# controller_rev4_3.net
KiCad netlist of a schematic drawn in EAGLE
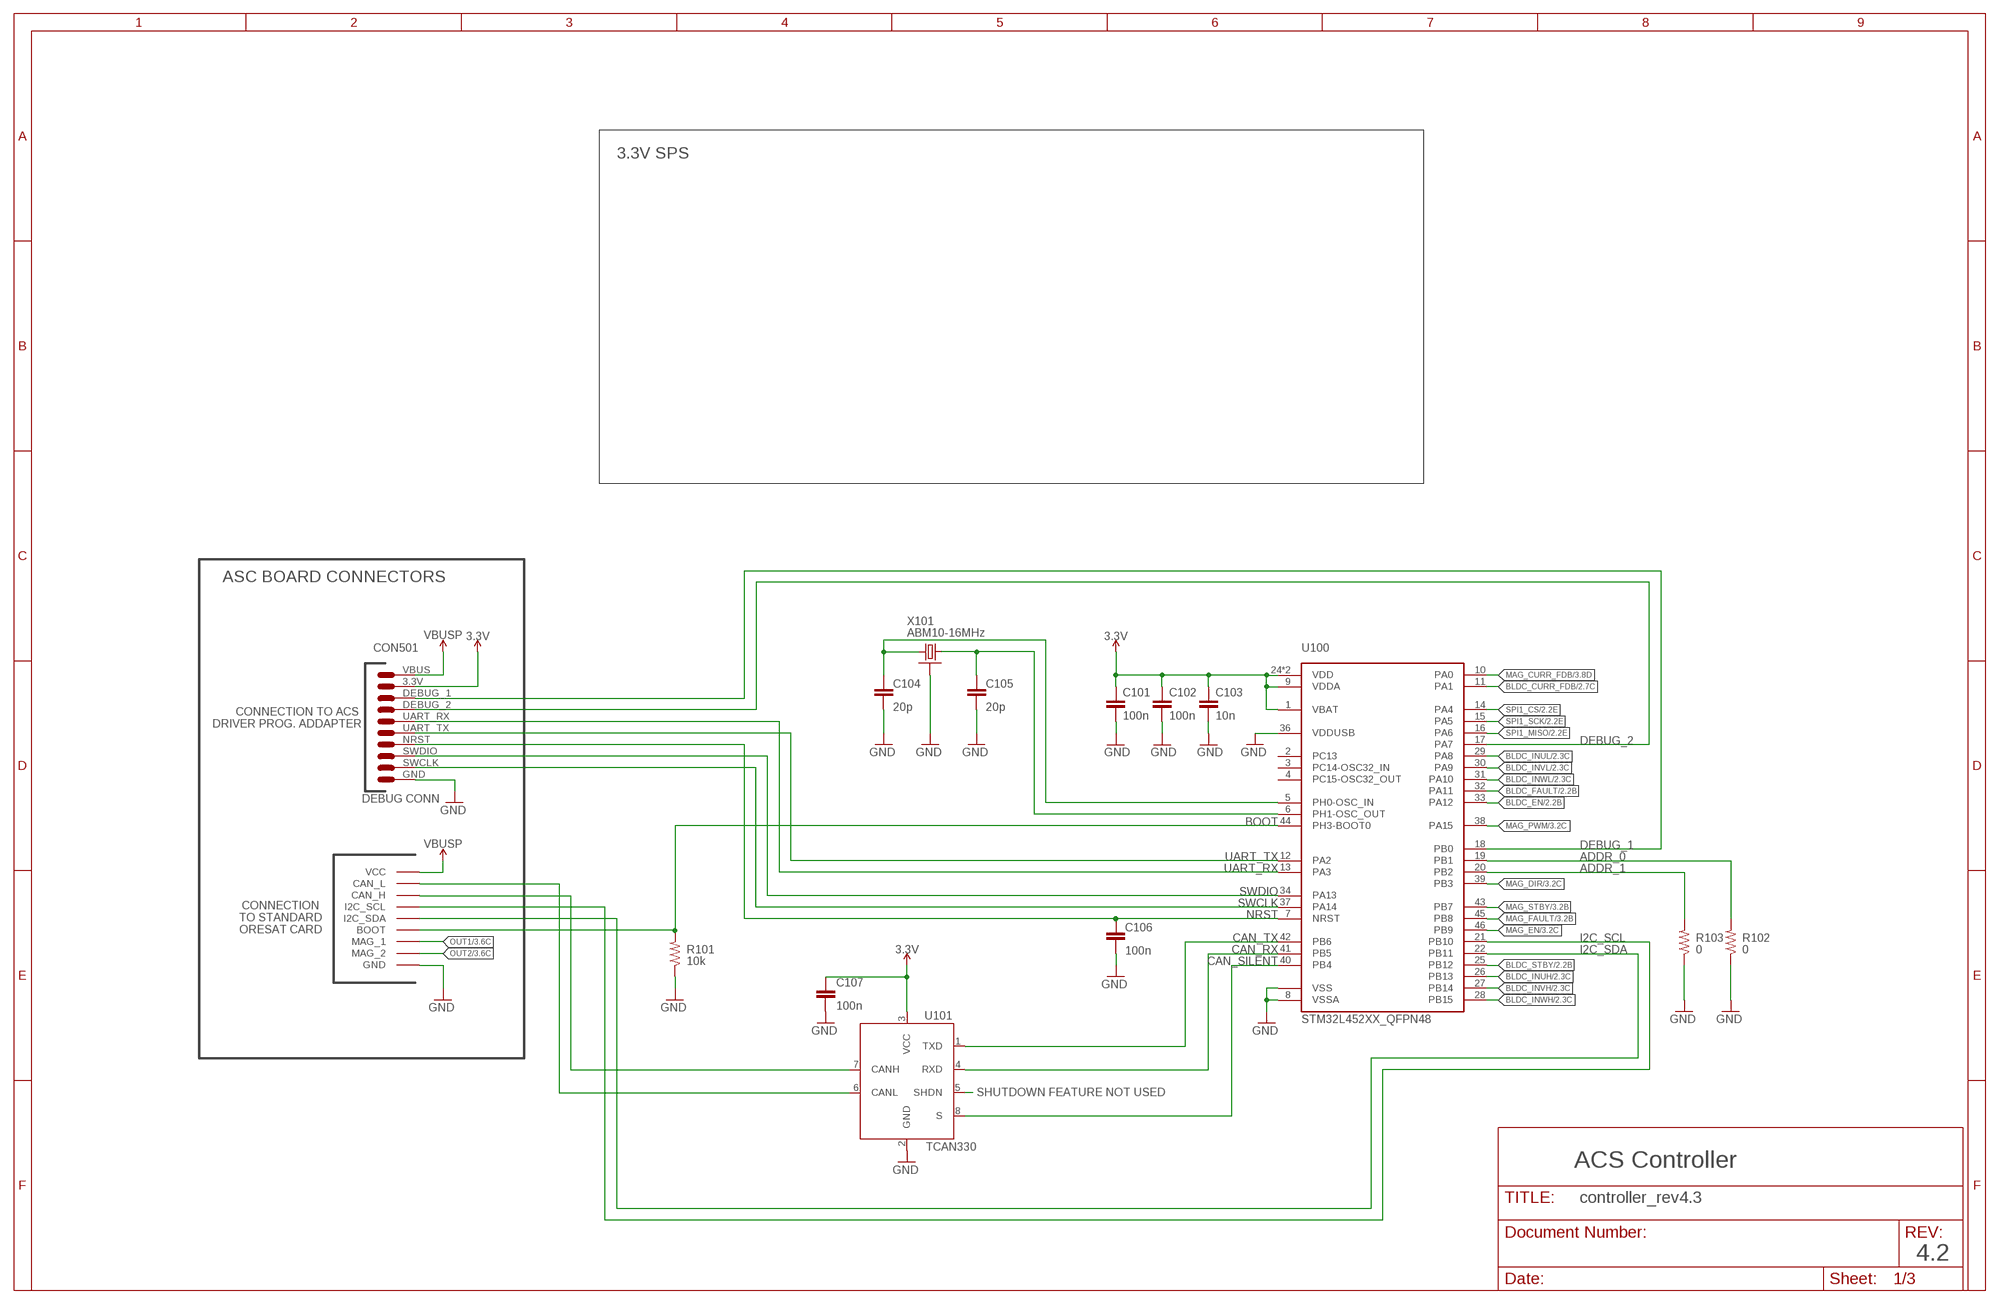
[diagram p0: schematic, sheet 1]
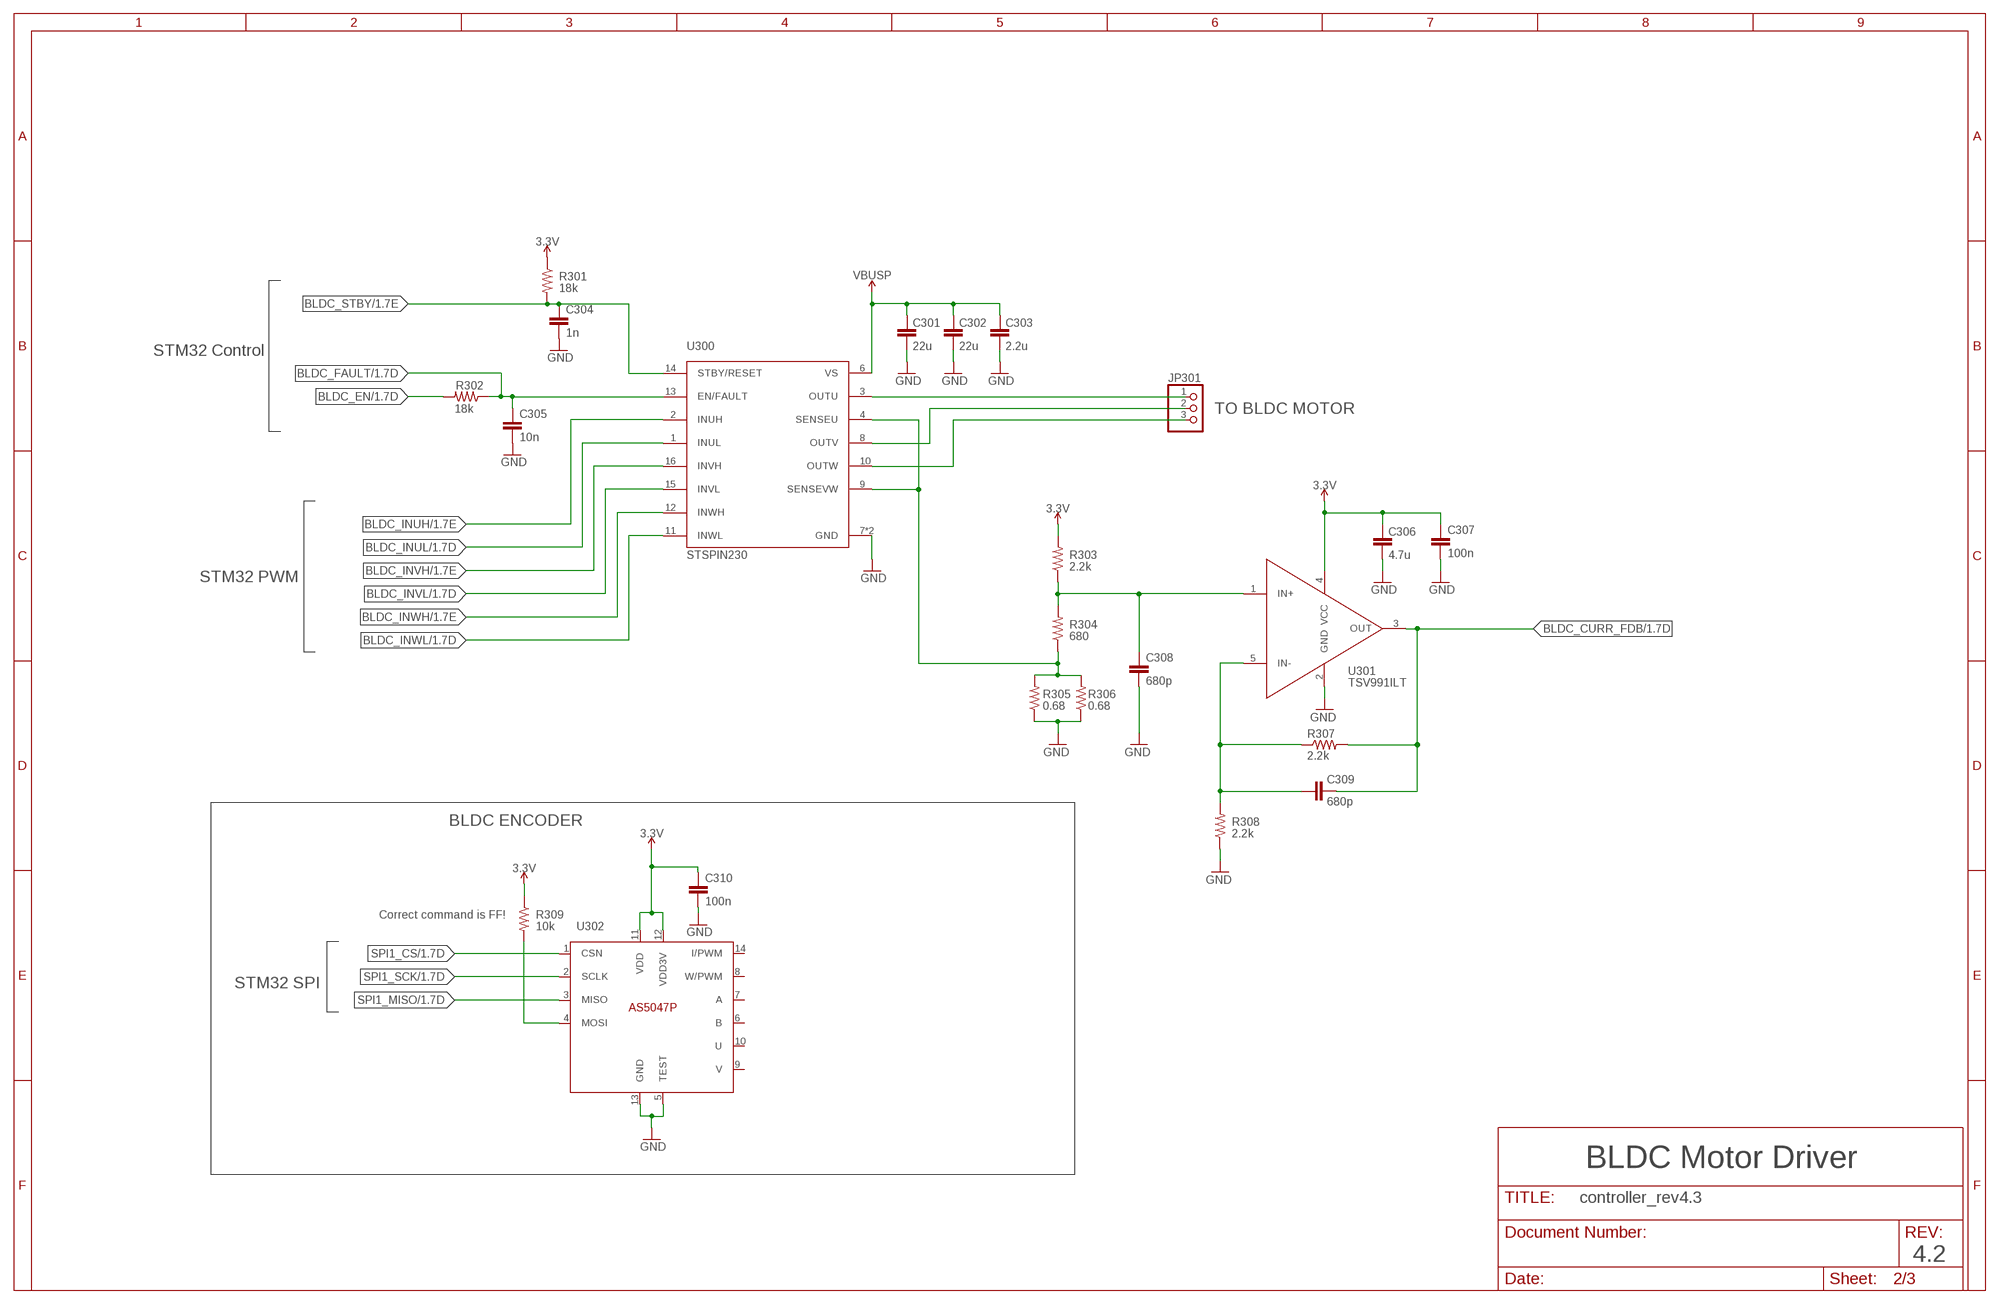
[diagram p1: schematic, sheet 2]
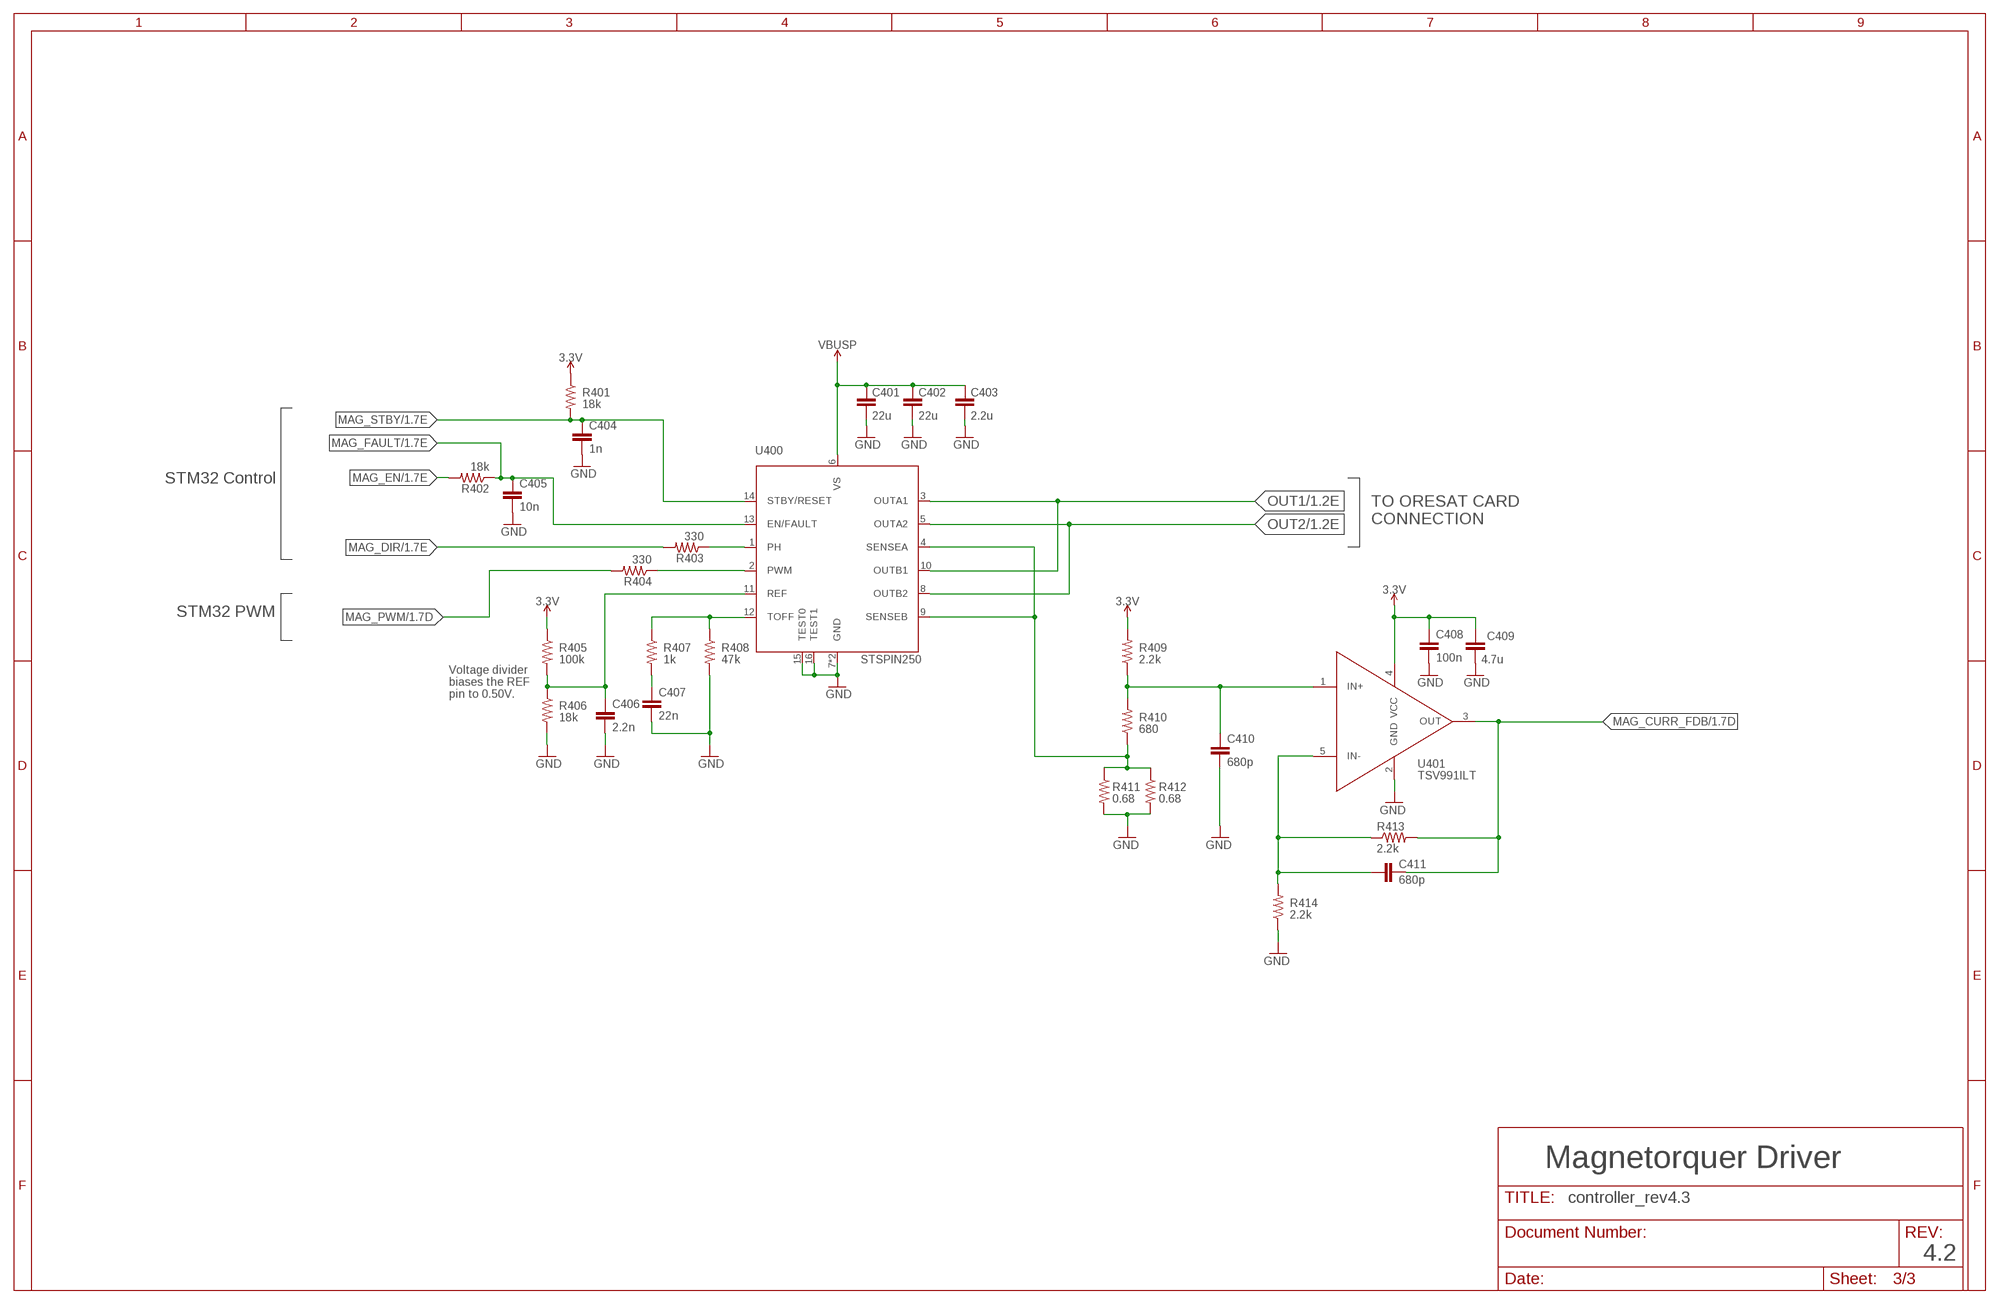
[diagram p2: schematic, sheet 3]

(export (version "E")
  (design (tool "Eeschema 10.0.6"))
  (components
    (comp (ref "C401")
      (value "22u")
      (footprint "eagle-import:.0603-B-NOSILK")
      (fields (field (name "MFR") "Samsung") (field (name "MPN") "CL05B104KO5NNNC"))
      (libsource (lib "eagle-import") (part "C-EU0603-B-NOSILK"))
    )
    (comp (ref "C402")
      (value "22u")
      (footprint "eagle-import:.0603-B-NOSILK")
      (fields (field (name "MFR") "Samsung") (field (name "MPN") "CL05B104KO5NNNC"))
      (libsource (lib "eagle-import") (part "C-EU0603-B-NOSILK"))
    )
    (comp (ref "C403")
      (value "2.2u")
      (footprint "eagle-import:.0603-B-NOSILK")
      (fields (field (name "MFR") "Samsung") (field (name "MPN") "CL05B104KO5NNNC"))
      (libsource (lib "eagle-import") (part "C-EU0603-B-NOSILK"))
    )
    (comp (ref "C404")
      (value "1n")
      (footprint "eagle-import:.0402-B-NOSILK")
      (fields (field (name "MFR") "Samsung") (field (name "MPN") "CL05B104KO5NNNC"))
      (libsource (lib "eagle-import") (part "rcl_custom_C-EU0402-B-NOSILK"))
    )
    (comp (ref "C405")
      (value "10n")
      (footprint "eagle-import:.0402-B-NOSILK")
      (fields (field (name "MFR") "Samsung") (field (name "MPN") "CL05B104KO5NNNC"))
      (libsource (lib "eagle-import") (part "rcl_custom_C-EU0402-B-NOSILK"))
    )
    (comp (ref "C406")
      (value "2.2n")
      (footprint "eagle-import:.0402-B-NOSILK")
      (fields (field (name "MFR") "Samsung") (field (name "MPN") "CL05B104KO5NNNC"))
      (libsource (lib "eagle-import") (part "rcl_custom_C-EU0402-B-NOSILK"))
    )
    (comp (ref "C407")
      (value "22n")
      (footprint "eagle-import:.0402-B-NOSILK")
      (fields (field (name "MFR") "Samsung") (field (name "MPN") "CL05B104KO5NNNC"))
      (libsource (lib "eagle-import") (part "rcl_custom_C-EU0402-B-NOSILK"))
    )
    (comp (ref "C408")
      (value "100n")
      (footprint "eagle-import:.0402-B-NOSILK")
      (fields (field (name "MFR") "Samsung") (field (name "MPN") "CL05B104KO5NNNC"))
      (libsource (lib "eagle-import") (part "rcl_custom_C-EU0402-B-NOSILK"))
    )
    (comp (ref "C409")
      (value "4.7u")
      (footprint "eagle-import:.0603-B-NOSILK")
      (fields (field (name "MFR") "Samsung") (field (name "MPN") "CL05B104KO5NNNC"))
      (libsource (lib "eagle-import") (part "C-EU0603-B-NOSILK"))
    )
    (comp (ref "C410")
      (value "680p")
      (footprint "eagle-import:.0402-B-NOSILK")
      (fields (field (name "MFR") "Samsung") (field (name "MPN") "CL05B104KO5NNNC"))
      (libsource (lib "eagle-import") (part "rcl_custom_C-EU0402-B-NOSILK"))
    )
    (comp (ref "C411")
      (value "680p")
      (footprint "eagle-import:.0402-B-NOSILK")
      (fields (field (name "MFR") "Samsung") (field (name "MPN") "CL05B104KO5NNNC"))
      (libsource (lib "eagle-import") (part "rcl_custom_C-EU0402-B-NOSILK"))
    )
    (comp (ref "R401")
      (value "18k")
      (footprint "eagle-import:.0402-B-NOSILK")
      (fields (field (name "MFR") "Samsung") (field (name "MPN") "RC1005F6653CS"))
      (libsource (lib "eagle-import") (part "rcl_custom_R-US_0402-B-NOSILK"))
    )
    (comp (ref "R402")
      (value "18k")
      (footprint "eagle-import:.0402-B-NOSILK")
      (fields (field (name "MFR") "Samsung") (field (name "MPN") "RC1005F6653CS"))
      (libsource (lib "eagle-import") (part "rcl_custom_R-US_0402-B-NOSILK"))
    )
    (comp (ref "R403")
      (value "330")
      (footprint "eagle-import:.0402-B-NOSILK")
      (fields (field (name "MFR") "Samsung") (field (name "MPN") "RC1005F6653CS"))
      (libsource (lib "eagle-import") (part "rcl_custom_R-US_0402-B-NOSILK"))
    )
    (comp (ref "R404")
      (value "330")
      (footprint "eagle-import:.0402-B-NOSILK")
      (fields (field (name "MFR") "Samsung") (field (name "MPN") "RC1005F6653CS"))
      (libsource (lib "eagle-import") (part "rcl_custom_R-US_0402-B-NOSILK"))
    )
    (comp (ref "R405")
      (value "100k")
      (footprint "eagle-import:.0402-B-NOSILK")
      (fields (field (name "MFR") "Samsung") (field (name "MPN") "RC1005F6653CS"))
      (libsource (lib "eagle-import") (part "rcl_custom_R-US_0402-B-NOSILK"))
    )
    (comp (ref "R406")
      (value "18k")
      (footprint "eagle-import:.0402-B-NOSILK")
      (fields (field (name "MFR") "Samsung") (field (name "MPN") "RC1005F6653CS"))
      (libsource (lib "eagle-import") (part "rcl_custom_R-US_0402-B-NOSILK"))
    )
    (comp (ref "R407")
      (value "1k")
      (footprint "eagle-import:.0402-B-NOSILK")
      (fields (field (name "MFR") "Samsung") (field (name "MPN") "RC1005F6653CS"))
      (libsource (lib "eagle-import") (part "rcl_custom_R-US_0402-B-NOSILK"))
    )
    (comp (ref "R408")
      (value "47k")
      (footprint "eagle-import:.0402-B-NOSILK")
      (fields (field (name "MFR") "Samsung") (field (name "MPN") "RC1005F6653CS"))
      (libsource (lib "eagle-import") (part "rcl_custom_R-US_0402-B-NOSILK"))
    )
    (comp (ref "R409")
      (value "2.2k")
      (footprint "eagle-import:.0402-B-NOSILK")
      (fields (field (name "MFR") "Samsung") (field (name "MPN") "RC1005F6653CS"))
      (libsource (lib "eagle-import") (part "rcl_custom_R-US_0402-B-NOSILK"))
    )
    (comp (ref "R410")
      (value "680")
      (footprint "eagle-import:.0402-B-NOSILK")
      (fields (field (name "MFR") "Samsung") (field (name "MPN") "RC1005F6653CS"))
      (libsource (lib "eagle-import") (part "rcl_custom_R-US_0402-B-NOSILK"))
    )
    (comp (ref "R411")
      (value "0.68")
      (footprint "eagle-import:.0805-B-NOSILK")
      (libsource (lib "eagle-import") (part "R-US_0805-B-NOSILK"))
    )
    (comp (ref "R412")
      (value "0.68")
      (footprint "eagle-import:.0805-B-NOSILK")
      (libsource (lib "eagle-import") (part "R-US_0805-B-NOSILK"))
    )
    (comp (ref "R413")
      (value "2.2k")
      (footprint "eagle-import:.0402-B-NOSILK")
      (fields (field (name "MFR") "Samsung") (field (name "MPN") "RC1005F6653CS"))
      (libsource (lib "eagle-import") (part "rcl_custom_R-US_0402-B-NOSILK"))
    )
    (comp (ref "R414")
      (value "2.2k")
      (footprint "eagle-import:.0402-B-NOSILK")
      (fields (field (name "MFR") "Samsung") (field (name "MPN") "RC1005F6653CS"))
      (libsource (lib "eagle-import") (part "rcl_custom_R-US_0402-B-NOSILK"))
    )
    (comp (ref "U400")
      (value "STSPIN250")
      (footprint "eagle-import:VFQPN")
      (libsource (lib "eagle-import") (part "STSPIN250"))
    )
    (comp (ref "U401")
      (value "TSV991ILT")
      (footprint "eagle-import:SOT23-5")
      (libsource (lib "eagle-import") (part "TSV991ILT"))
    )
    (comp (ref "C101")
      (value "100n")
      (footprint "eagle-import:.0402-B-NOSILK")
      (fields (field (name "MFR") "Samsung") (field (name "MPN") "CL05B104KO5NNNC"))
      (libsource (lib "eagle-import") (part "rcl_custom_C-EU0402-B-NOSILK"))
    )
    (comp (ref "C102")
      (value "100n")
      (footprint "eagle-import:.0402-B-NOSILK")
      (fields (field (name "MFR") "Samsung") (field (name "MPN") "CL05B104KO5NNNC"))
      (libsource (lib "eagle-import") (part "rcl_custom_C-EU0402-B-NOSILK"))
    )
    (comp (ref "C103")
      (value "10n")
      (footprint "eagle-import:.0402-B-NOSILK")
      (fields (field (name "MFR") "Samsung") (field (name "MPN") "CL05B104KO5NNNC"))
      (libsource (lib "eagle-import") (part "rcl_custom_C-EU0402-B-NOSILK"))
    )
    (comp (ref "C104")
      (value "20p")
      (footprint "eagle-import:.0402-B-NOSILK")
      (fields (field (name "MFR") "Samsung") (field (name "MPN") "CL05C200JB51PNC"))
      (libsource (lib "eagle-import") (part "rcl_custom_C-EU0402-B-NOSILK"))
    )
    (comp (ref "C105")
      (value "20p")
      (footprint "eagle-import:.0402-B-NOSILK")
      (fields (field (name "MFR") "Samsung") (field (name "MPN") "CL05C200JB51PNC"))
      (libsource (lib "eagle-import") (part "rcl_custom_C-EU0402-B-NOSILK"))
    )
    (comp (ref "C106")
      (value "100n")
      (footprint "eagle-import:.0402-B-NOSILK")
      (fields (field (name "MFR") "Samsung") (field (name "MPN") "CL05C200JB51PNC"))
      (libsource (lib "eagle-import") (part "rcl_custom_C-EU0402-B-NOSILK"))
    )
    (comp (ref "C107")
      (value "100n")
      (footprint "eagle-import:.0402-B-NOSILK")
      (fields (field (name "MFR") "Samsung") (field (name "MPN") "CL05B104KO5NNNC"))
      (libsource (lib "eagle-import") (part "rcl_custom_C-EU0402-B-NOSILK"))
    )
    (comp (ref "C501")
      (value "DEBUG_CON")
      (footprint "eagle-import:DEBUG_CON")
      (libsource (lib "eagle-import") (part "DEBUG_CON"))
    )
    (comp (ref "R101")
      (value "10k")
      (footprint "eagle-import:.0402-B-NOSILK")
      (fields (field (name "MFR") "Samsung") (field (name "MPN") "RC1005F6653CS"))
      (libsource (lib "eagle-import") (part "rcl_custom_R-US_0402-B-NOSILK"))
    )
    (comp (ref "R102")
      (value "0")
      (footprint "eagle-import:.0402-B-NOSILK")
      (fields (field (name "MFR") "Samsung") (field (name "MPN") "RC1005F6653CS"))
      (libsource (lib "eagle-import") (part "rcl_custom_R-US_0402-B-NOSILK"))
    )
    (comp (ref "R103")
      (value "0")
      (footprint "eagle-import:.0402-B-NOSILK")
      (fields (field (name "MFR") "Samsung") (field (name "MPN") "RC1005F6653CS"))
      (libsource (lib "eagle-import") (part "rcl_custom_R-US_0402-B-NOSILK"))
    )
    (comp (ref "U$2")
      (value "MEZZANINE_1")
      (footprint "eagle-import:MEZZANINE_1")
      (libsource (lib "eagle-import") (part "MEZZANINE_1"))
    )
    (comp (ref "U100")
      (value "STM32L452XX_QFPN48")
      (footprint "eagle-import:QFPN-48")
      (libsource (lib "eagle-import") (part "STM32L452XX_QFPN48"))
    )
    (comp (ref "U101")
      (value "TCAN330")
      (footprint "eagle-import:SOT23-8_TI-DCN")
      (fields (field (name "MFR") "Texas Instruments") (field (name "MPN") "TCAN330GDCNT"))
      (libsource (lib "eagle-import") (part "TCAN330"))
    )
    (comp (ref "X101")
      (value "ABM10-16MHz")
      (footprint "eagle-import:CRYSTAL_2.5X2")
      (fields (field (name "MFR") "ECS Inc.") (field (name "MPN") "ECS-160-10-36Q-ES-TR"))
      (libsource (lib "eagle-import") (part "CRYSTAL-WITH-GND"))
    )
    (comp (ref "C301")
      (value "22u")
      (footprint "eagle-import:.0603-B-NOSILK")
      (fields (field (name "MFR") "Samsung") (field (name "MPN") "CL05B104KO5NNNC"))
      (libsource (lib "eagle-import") (part "C-EU0603-B-NOSILK"))
    )
    (comp (ref "C302")
      (value "22u")
      (footprint "eagle-import:.0603-B-NOSILK")
      (fields (field (name "MFR") "Samsung") (field (name "MPN") "CL05B104KO5NNNC"))
      (libsource (lib "eagle-import") (part "C-EU0603-B-NOSILK"))
    )
    (comp (ref "C303")
      (value "2.2u")
      (footprint "eagle-import:.0603-B-NOSILK")
      (fields (field (name "MFR") "Samsung") (field (name "MPN") "CL05B104KO5NNNC"))
      (libsource (lib "eagle-import") (part "C-EU0603-B-NOSILK"))
    )
    (comp (ref "C304")
      (value "1n")
      (footprint "eagle-import:.0402-B-NOSILK")
      (fields (field (name "MFR") "Samsung") (field (name "MPN") "CL05B104KO5NNNC"))
      (libsource (lib "eagle-import") (part "rcl_custom_C-EU0402-B-NOSILK"))
    )
    (comp (ref "C305")
      (value "10n")
      (footprint "eagle-import:.0402-B-NOSILK")
      (fields (field (name "MFR") "Samsung") (field (name "MPN") "CL05B104KO5NNNC"))
      (libsource (lib "eagle-import") (part "rcl_custom_C-EU0402-B-NOSILK"))
    )
    (comp (ref "C306")
      (value "4.7u")
      (footprint "eagle-import:.0603-B-NOSILK")
      (fields (field (name "MFR") "Samsung") (field (name "MPN") "CL05B104KO5NNNC"))
      (libsource (lib "eagle-import") (part "C-EU0603-B-NOSILK"))
    )
    (comp (ref "C307")
      (value "100n")
      (footprint "eagle-import:.0402-B-NOSILK")
      (fields (field (name "MFR") "Samsung") (field (name "MPN") "CL05B104KO5NNNC"))
      (libsource (lib "eagle-import") (part "rcl_custom_C-EU0402-B-NOSILK"))
    )
    (comp (ref "C308")
      (value "680p")
      (footprint "eagle-import:.0402-B-NOSILK")
      (fields (field (name "MFR") "Samsung") (field (name "MPN") "CL05B104KO5NNNC"))
      (libsource (lib "eagle-import") (part "rcl_custom_C-EU0402-B-NOSILK"))
    )
    (comp (ref "C309")
      (value "680p")
      (footprint "eagle-import:.0402-B-NOSILK")
      (fields (field (name "MFR") "Samsung") (field (name "MPN") "CL05B104KO5NNNC"))
      (libsource (lib "eagle-import") (part "rcl_custom_C-EU0402-B-NOSILK"))
    )
    (comp (ref "C310")
      (value "100n")
      (footprint "eagle-import:.0402-B-NOSILK")
      (fields (field (name "MFR") "Samsung") (field (name "MPN") "CL05B104KO5NNNC"))
      (libsource (lib "eagle-import") (part "rcl_custom_C-EU0402-B-NOSILK"))
    )
    (comp (ref "JP301")
      (value "PINHD-1X03_2.00")
      (footprint "eagle-import:1X03M")
      (libsource (lib "eagle-import") (part "PINHD-1X03_2.00"))
    )
    (comp (ref "R301")
      (value "18k")
      (footprint "eagle-import:.0402-B-NOSILK")
      (fields (field (name "MFR") "Samsung") (field (name "MPN") "RC1005F6653CS"))
      (libsource (lib "eagle-import") (part "rcl_custom_R-US_0402-B-NOSILK"))
    )
    (comp (ref "R302")
      (value "18k")
      (footprint "eagle-import:.0402-B-NOSILK")
      (fields (field (name "MFR") "Samsung") (field (name "MPN") "RC1005F6653CS"))
      (libsource (lib "eagle-import") (part "rcl_custom_R-US_0402-B-NOSILK"))
    )
    (comp (ref "R303")
      (value "2.2k")
      (footprint "eagle-import:.0402-B-NOSILK")
      (fields (field (name "MFR") "Samsung") (field (name "MPN") "RC1005F6653CS"))
      (libsource (lib "eagle-import") (part "rcl_custom_R-US_0402-B-NOSILK"))
    )
    (comp (ref "R304")
      (value "680")
      (footprint "eagle-import:.0402-B-NOSILK")
      (fields (field (name "MFR") "Samsung") (field (name "MPN") "RC1005F6653CS"))
      (libsource (lib "eagle-import") (part "rcl_custom_R-US_0402-B-NOSILK"))
    )
    (comp (ref "R305")
      (value "0.68")
      (footprint "eagle-import:.0805-B-NOSILK")
      (libsource (lib "eagle-import") (part "R-US_0805-B-NOSILK"))
    )
    (comp (ref "R306")
      (value "0.68")
      (footprint "eagle-import:.0805-B-NOSILK")
      (libsource (lib "eagle-import") (part "R-US_0805-B-NOSILK"))
    )
    (comp (ref "R307")
      (value "2.2k")
      (footprint "eagle-import:.0402-B-NOSILK")
      (fields (field (name "MFR") "Samsung") (field (name "MPN") "RC1005F6653CS"))
      (libsource (lib "eagle-import") (part "rcl_custom_R-US_0402-B-NOSILK"))
    )
    (comp (ref "R308")
      (value "2.2k")
      (footprint "eagle-import:.0402-B-NOSILK")
      (fields (field (name "MFR") "Samsung") (field (name "MPN") "RC1005F6653CS"))
      (libsource (lib "eagle-import") (part "rcl_custom_R-US_0402-B-NOSILK"))
    )
    (comp (ref "R309")
      (value "10k")
      (footprint "eagle-import:.0402-B-NOSILK")
      (fields (field (name "MFR") "Samsung") (field (name "MPN") "RC1005F6653CS"))
      (libsource (lib "eagle-import") (part "rcl_custom_R-US_0402-B-NOSILK"))
    )
    (comp (ref "U300")
      (value "STSPIN230")
      (footprint "eagle-import:VFQPN")
      (libsource (lib "eagle-import") (part "STSPIN230"))
    )
    (comp (ref "U301")
      (value "TSV991ILT")
      (footprint "eagle-import:SOT23-5")
      (libsource (lib "eagle-import") (part "TSV991ILT"))
    )
    (comp (ref "U302")
      (value "AS5047P")
      (footprint "eagle-import:TSSOP14")
      (libsource (lib "eagle-import") (part "AS5047P"))
    )
  )
  (nets
    (net (code "1") (name "3.3V") (class "Default")
      (node (ref "C101") (pin "1") (pinfunction "1_1") (pintype "passive"))
      (node (ref "C102") (pin "1") (pinfunction "1_1") (pintype "passive"))
      (node (ref "C103") (pin "1") (pinfunction "1_1") (pintype "passive"))
      (node (ref "C107") (pin "1") (pinfunction "1_1") (pintype "passive"))
      (node (ref "C306") (pin "1") (pinfunction "1_1") (pintype "passive"))
      (node (ref "C307") (pin "1") (pinfunction "1_1") (pintype "passive"))
      (node (ref "C310") (pin "1") (pinfunction "1_1") (pintype "passive"))
      (node (ref "C408") (pin "1") (pinfunction "1_1") (pintype "passive"))
      (node (ref "C409") (pin "1") (pinfunction "1_1") (pintype "passive"))
      (node (ref "C501") (pin "3.3V") (pinfunction "2_3.3V") (pintype "bidirectional"))
      (node (ref "R301") (pin "1") (pinfunction "1_1") (pintype "passive"))
      (node (ref "R303") (pin "2") (pinfunction "2_2") (pintype "passive"))
      (node (ref "R309") (pin "1") (pinfunction "1_1") (pintype "passive"))
      (node (ref "R401") (pin "1") (pinfunction "1_1") (pintype "passive"))
      (node (ref "R405") (pin "1") (pinfunction "1_1") (pintype "passive"))
      (node (ref "R409") (pin "2") (pinfunction "2_2") (pintype "passive"))
      (node (ref "U100") (pin "1") (pinfunction "VBAT_1") (pintype "bidirectional"))
      (node (ref "U100") (pin "24") (pinfunction "VDD_24") (pintype "bidirectional"))
      (node (ref "U100") (pin "48") (pinfunction "VDD_48") (pintype "bidirectional"))
      (node (ref "U100") (pin "9") (pinfunction "VDDA_9") (pintype "bidirectional"))
      (node (ref "U101") (pin "3") (pinfunction "VCC_3") (pintype "power_in"))
      (node (ref "U301") (pin "4") (pinfunction "VCC_4") (pintype "bidirectional"))
      (node (ref "U302") (pin "11") (pinfunction "VDD_11") (pintype "power_in"))
      (node (ref "U302") (pin "12") (pinfunction "VDD3V_12") (pintype "power_in"))
      (node (ref "U401") (pin "4") (pinfunction "VCC_4") (pintype "bidirectional"))
    )
    (net (code "2") (name "ADDR_0") (class "Default")
      (node (ref "R102") (pin "2") (pinfunction "2_2") (pintype "passive"))
      (node (ref "U100") (pin "19") (pinfunction "PB1_19") (pintype "bidirectional"))
    )
    (net (code "3") (name "ADDR_1") (class "Default")
      (node (ref "R103") (pin "2") (pinfunction "2_2") (pintype "passive"))
      (node (ref "U100") (pin "20") (pinfunction "PB2_20") (pintype "bidirectional"))
    )
    (net (code "4") (name "BLDC_CURR_FDB") (class "Default")
      (node (ref "C309") (pin "1") (pinfunction "1_1") (pintype "passive"))
      (node (ref "R307") (pin "2") (pinfunction "2_2") (pintype "passive"))
      (node (ref "U100") (pin "11") (pinfunction "PA1_11") (pintype "bidirectional"))
      (node (ref "U301") (pin "3") (pinfunction "OUT_3") (pintype "bidirectional"))
    )
    (net (code "5") (name "BLDC_EN") (class "Default")
      (node (ref "R302") (pin "2") (pinfunction "2_2") (pintype "passive"))
      (node (ref "U100") (pin "33") (pinfunction "PA12_33") (pintype "bidirectional"))
    )
    (net (code "6") (name "BLDC_FAULT") (class "Default")
      (node (ref "C305") (pin "1") (pinfunction "1_1") (pintype "passive"))
      (node (ref "R302") (pin "1") (pinfunction "1_1") (pintype "passive"))
      (node (ref "U100") (pin "32") (pinfunction "PA11_32") (pintype "bidirectional"))
      (node (ref "U300") (pin "13") (pinfunction "EN/FAULT_13") (pintype "bidirectional"))
    )
    (net (code "7") (name "BLDC_INUH") (class "Default")
      (node (ref "U100") (pin "26") (pinfunction "PB13_26") (pintype "bidirectional"))
      (node (ref "U300") (pin "2") (pinfunction "INUH_2") (pintype "input"))
    )
    (net (code "8") (name "BLDC_INUL") (class "Default")
      (node (ref "U100") (pin "29") (pinfunction "PA8_29") (pintype "bidirectional"))
      (node (ref "U300") (pin "1") (pinfunction "INUL_1") (pintype "input"))
    )
    (net (code "9") (name "BLDC_INVH") (class "Default")
      (node (ref "U100") (pin "27") (pinfunction "PB14_27") (pintype "bidirectional"))
      (node (ref "U300") (pin "16") (pinfunction "INVH_16") (pintype "input"))
    )
    (net (code "10") (name "BLDC_INVL") (class "Default")
      (node (ref "U100") (pin "30") (pinfunction "PA9_30") (pintype "bidirectional"))
      (node (ref "U300") (pin "15") (pinfunction "INVL_15") (pintype "input"))
    )
    (net (code "11") (name "BLDC_INWH") (class "Default")
      (node (ref "U100") (pin "28") (pinfunction "PB15_28") (pintype "bidirectional"))
      (node (ref "U300") (pin "12") (pinfunction "INWH_12") (pintype "input"))
    )
    (net (code "12") (name "BLDC_INWL") (class "Default")
      (node (ref "U100") (pin "31") (pinfunction "PA10_31") (pintype "bidirectional"))
      (node (ref "U300") (pin "11") (pinfunction "INWL_11") (pintype "input"))
    )
    (net (code "13") (name "BLDC_STBY") (class "Default")
      (node (ref "C304") (pin "1") (pinfunction "1_1") (pintype "passive"))
      (node (ref "R301") (pin "2") (pinfunction "2_2") (pintype "passive"))
      (node (ref "U100") (pin "25") (pinfunction "PB12_25") (pintype "bidirectional"))
      (node (ref "U300") (pin "14") (pinfunction "STBY/RESET_14") (pintype "input"))
    )
    (net (code "14") (name "BOOT") (class "Default")
      (node (ref "R101") (pin "2") (pinfunction "2_2") (pintype "passive"))
      (node (ref "U$2") (pin "P$22") (pinfunction "BOOT_P$22") (pintype "bidirectional"))
      (node (ref "U$2") (pin "P$9") (pinfunction "BOOT_P$9") (pintype "bidirectional"))
      (node (ref "U100") (pin "44") (pinfunction "PH3-BOOT0_44") (pintype "bidirectional"))
    )
    (net (code "15") (name "CAN_RX") (class "Default")
      (node (ref "U100") (pin "41") (pinfunction "PB5_41") (pintype "bidirectional"))
      (node (ref "U101") (pin "4") (pinfunction "RXD_4") (pintype "output"))
    )
    (net (code "16") (name "CAN_SILENT") (class "Default")
      (node (ref "U100") (pin "40") (pinfunction "PB4_40") (pintype "bidirectional"))
      (node (ref "U101") (pin "8") (pinfunction "S_8") (pintype "input"))
    )
    (net (code "17") (name "CAN_TX") (class "Default")
      (node (ref "U100") (pin "42") (pinfunction "PB6_42") (pintype "bidirectional"))
      (node (ref "U101") (pin "1") (pinfunction "TXD_1") (pintype "input"))
    )
    (net (code "18") (name "DEBUG_1") (class "Default")
      (node (ref "C501") (pin "DEBUG_1") (pinfunction "3_DEBUG_1") (pintype "bidirectional"))
      (node (ref "U100") (pin "18") (pinfunction "PB0_18") (pintype "bidirectional"))
    )
    (net (code "19") (name "DEBUG_2") (class "Default")
      (node (ref "C501") (pin "DEBUG_2") (pinfunction "4_DEBUG_2") (pintype "bidirectional"))
      (node (ref "U100") (pin "17") (pinfunction "PA7_17") (pintype "bidirectional"))
    )
    (net (code "20") (name "GND") (class "Default")
      (node (ref "C101") (pin "2") (pinfunction "2_2") (pintype "passive"))
      (node (ref "C102") (pin "2") (pinfunction "2_2") (pintype "passive"))
      (node (ref "C103") (pin "2") (pinfunction "2_2") (pintype "passive"))
      (node (ref "C104") (pin "2") (pinfunction "2_2") (pintype "passive"))
      (node (ref "C105") (pin "2") (pinfunction "2_2") (pintype "passive"))
      (node (ref "C106") (pin "2") (pinfunction "2_2") (pintype "passive"))
      (node (ref "C107") (pin "2") (pinfunction "2_2") (pintype "passive"))
      (node (ref "C301") (pin "2") (pinfunction "2_2") (pintype "passive"))
      (node (ref "C302") (pin "2") (pinfunction "2_2") (pintype "passive"))
      (node (ref "C303") (pin "2") (pinfunction "2_2") (pintype "passive"))
      (node (ref "C304") (pin "2") (pinfunction "2_2") (pintype "passive"))
      (node (ref "C305") (pin "2") (pinfunction "2_2") (pintype "passive"))
      (node (ref "C306") (pin "2") (pinfunction "2_2") (pintype "passive"))
      (node (ref "C307") (pin "2") (pinfunction "2_2") (pintype "passive"))
      (node (ref "C308") (pin "2") (pinfunction "2_2") (pintype "passive"))
      (node (ref "C310") (pin "2") (pinfunction "2_2") (pintype "passive"))
      (node (ref "C401") (pin "2") (pinfunction "2_2") (pintype "passive"))
      (node (ref "C402") (pin "2") (pinfunction "2_2") (pintype "passive"))
      (node (ref "C403") (pin "2") (pinfunction "2_2") (pintype "passive"))
      (node (ref "C404") (pin "2") (pinfunction "2_2") (pintype "passive"))
      (node (ref "C405") (pin "2") (pinfunction "2_2") (pintype "passive"))
      (node (ref "C406") (pin "2") (pinfunction "2_2") (pintype "passive"))
      (node (ref "C407") (pin "2") (pinfunction "2_2") (pintype "passive"))
      (node (ref "C408") (pin "2") (pinfunction "2_2") (pintype "passive"))
      (node (ref "C409") (pin "2") (pinfunction "2_2") (pintype "passive"))
      (node (ref "C410") (pin "2") (pinfunction "2_2") (pintype "passive"))
      (node (ref "C501") (pin "GND") (pinfunction "10_GND") (pintype "bidirectional"))
      (node (ref "R101") (pin "1") (pinfunction "1_1") (pintype "passive"))
      (node (ref "R102") (pin "1") (pinfunction "1_1") (pintype "passive"))
      (node (ref "R103") (pin "1") (pinfunction "1_1") (pintype "passive"))
      (node (ref "R305") (pin "1") (pinfunction "1_1") (pintype "passive"))
      (node (ref "R306") (pin "1") (pinfunction "1_1") (pintype "passive"))
      (node (ref "R308") (pin "1") (pinfunction "1_1") (pintype "passive"))
      (node (ref "R406") (pin "2") (pinfunction "2_2") (pintype "passive"))
      (node (ref "R408") (pin "2") (pinfunction "2_2") (pintype "passive"))
      (node (ref "R411") (pin "2") (pinfunction "2_2") (pintype "passive"))
      (node (ref "R412") (pin "2") (pinfunction "2_2") (pintype "passive"))
      (node (ref "R414") (pin "1") (pinfunction "1_1") (pintype "passive"))
      (node (ref "U$2") (pin "P$1") (pinfunction "GND_P$1") (pintype "bidirectional"))
      (node (ref "U$2") (pin "P$14") (pinfunction "GND_P$14") (pintype "bidirectional"))
      (node (ref "U$2") (pin "P$15") (pinfunction "GND_P$15") (pintype "bidirectional"))
      (node (ref "U$2") (pin "P$16") (pinfunction "GND_P$16") (pintype "bidirectional"))
      (node (ref "U$2") (pin "P$17") (pinfunction "GND_P$17") (pintype "bidirectional"))
      (node (ref "U$2") (pin "P$2") (pinfunction "GND_P$2") (pintype "bidirectional"))
      (node (ref "U$2") (pin "P$29") (pinfunction "GND_P$29") (pintype "bidirectional"))
      (node (ref "U$2") (pin "P$30") (pinfunction "GND_P$30") (pintype "bidirectional"))
      (node (ref "U100") (pin "23") (pinfunction "VSS_23") (pintype "bidirectional"))
      (node (ref "U100") (pin "35") (pinfunction "VSS_35") (pintype "bidirectional"))
      (node (ref "U100") (pin "36") (pinfunction "VDDUSB_36") (pintype "bidirectional"))
      (node (ref "U100") (pin "47") (pinfunction "VSS_47") (pintype "bidirectional"))
      (node (ref "U100") (pin "8") (pinfunction "VSSA_8") (pintype "bidirectional"))
      (node (ref "U100") (pin "EPAD") (pinfunction "VSS_EPAD") (pintype "bidirectional"))
      (node (ref "U101") (pin "2") (pinfunction "GND_2") (pintype "power_in"))
      (node (ref "U300") (pin "7") (pinfunction "GND_7") (pintype "power_in"))
      (node (ref "U300") (pin "EPAD") (pinfunction "GND_EPAD") (pintype "power_in"))
      (node (ref "U301") (pin "2") (pinfunction "GND_2") (pintype "bidirectional"))
      (node (ref "U302") (pin "13") (pinfunction "GND_13") (pintype "power_in"))
      (node (ref "U302") (pin "5") (pinfunction "TEST_5") (pintype "power_in"))
      (node (ref "U400") (pin "15") (pinfunction "TEST0_15") (pintype "bidirectional"))
      (node (ref "U400") (pin "16") (pinfunction "TEST1_16") (pintype "bidirectional"))
      (node (ref "U400") (pin "7") (pinfunction "GND_7") (pintype "power_in"))
      (node (ref "U400") (pin "EPAD") (pinfunction "GND_EPAD") (pintype "power_in"))
      (node (ref "U401") (pin "2") (pinfunction "GND_2") (pintype "bidirectional"))
      (node (ref "X101") (pin "2") (pinfunction "SHIELD_2") (pintype "power_in"))
      (node (ref "X101") (pin "4") (pinfunction "SHIELD_4") (pintype "power_in"))
    )
    (net (code "21") (name "I2C_SCL") (class "Default")
      (node (ref "U$2") (pin "P$24") (pinfunction "I2C_SCL_P$24") (pintype "bidirectional"))
      (node (ref "U$2") (pin "P$7") (pinfunction "I2C_SCL_P$7") (pintype "bidirectional"))
      (node (ref "U100") (pin "21") (pinfunction "PB10_21") (pintype "bidirectional"))
    )
    (net (code "22") (name "I2C_SDA") (class "Default")
      (node (ref "U$2") (pin "P$23") (pinfunction "I2C_SDA_P$23") (pintype "bidirectional"))
      (node (ref "U$2") (pin "P$8") (pinfunction "I2C_SDA_P$8") (pintype "bidirectional"))
      (node (ref "U100") (pin "22") (pinfunction "PB11_22") (pintype "bidirectional"))
    )
    (net (code "23") (name "MAG_CURR_FDB") (class "Default")
      (node (ref "C411") (pin "1") (pinfunction "1_1") (pintype "passive"))
      (node (ref "R413") (pin "2") (pinfunction "2_2") (pintype "passive"))
      (node (ref "U100") (pin "10") (pinfunction "PA0_10") (pintype "bidirectional"))
      (node (ref "U401") (pin "3") (pinfunction "OUT_3") (pintype "bidirectional"))
    )
    (net (code "24") (name "MAG_DIR") (class "Default")
      (node (ref "R403") (pin "2") (pinfunction "2_2") (pintype "passive"))
      (node (ref "U100") (pin "39") (pinfunction "PB3_39") (pintype "bidirectional"))
    )
    (net (code "25") (name "MAG_EN") (class "Default")
      (node (ref "R402") (pin "2") (pinfunction "2_2") (pintype "passive"))
      (node (ref "U100") (pin "46") (pinfunction "PB9_46") (pintype "bidirectional"))
    )
    (net (code "26") (name "MAG_FAULT") (class "Default")
      (node (ref "C405") (pin "1") (pinfunction "1_1") (pintype "passive"))
      (node (ref "R402") (pin "1") (pinfunction "1_1") (pintype "passive"))
      (node (ref "U100") (pin "45") (pinfunction "PB8_45") (pintype "bidirectional"))
      (node (ref "U400") (pin "13") (pinfunction "EN/FAULT_13") (pintype "bidirectional"))
    )
    (net (code "27") (name "MAG_PWM") (class "Default")
      (node (ref "R404") (pin "2") (pinfunction "2_2") (pintype "passive"))
      (node (ref "U100") (pin "38") (pinfunction "PA15_38") (pintype "bidirectional"))
    )
    (net (code "28") (name "MAG_STBY") (class "Default")
      (node (ref "C404") (pin "1") (pinfunction "1_1") (pintype "passive"))
      (node (ref "R401") (pin "2") (pinfunction "2_2") (pintype "passive"))
      (node (ref "U100") (pin "43") (pinfunction "PB7_43") (pintype "bidirectional"))
      (node (ref "U400") (pin "14") (pinfunction "STBY/RESET_14") (pintype "bidirectional"))
    )
    (net (code "29") (name "NRST") (class "Default")
      (node (ref "C106") (pin "1") (pinfunction "1_1") (pintype "passive"))
      (node (ref "C501") (pin "NRST") (pinfunction "7_NRST") (pintype "bidirectional"))
      (node (ref "U100") (pin "7") (pinfunction "NRST_7") (pintype "bidirectional"))
    )
    (net (code "30") (name "Net-(C407-Pad1)") (class "Default")
      (node (ref "C407") (pin "1") (pinfunction "1_1") (pintype "passive"))
      (node (ref "R407") (pin "2") (pinfunction "2_2") (pintype "passive"))
    )
    (net (code "31") (name "Net-(U100-PH0-OSC_IN)") (class "Default")
      (node (ref "C104") (pin "1") (pinfunction "1_1") (pintype "passive"))
      (node (ref "U100") (pin "5") (pinfunction "PH0-OSC_IN_5") (pintype "bidirectional"))
      (node (ref "X101") (pin "3") (pinfunction "2_3") (pintype "passive"))
    )
    (net (code "32") (name "Net-(U100-PH1-OSC_OUT)") (class "Default")
      (node (ref "C105") (pin "1") (pinfunction "1_1") (pintype "passive"))
      (node (ref "U100") (pin "6") (pinfunction "PH1-OSC_OUT_6") (pintype "bidirectional"))
      (node (ref "X101") (pin "1") (pinfunction "1_1") (pintype "passive"))
    )
    (net (code "33") (name "Net-(U101-CANH)") (class "Default")
      (node (ref "U$2") (pin "P$25") (pinfunction "CAN_H_P$25") (pintype "bidirectional"))
      (node (ref "U$2") (pin "P$6") (pinfunction "CAN_H_P$6") (pintype "bidirectional"))
      (node (ref "U101") (pin "7") (pinfunction "CANH_7") (pintype "bidirectional"))
    )
    (net (code "34") (name "Net-(U101-CANL)") (class "Default")
      (node (ref "U$2") (pin "P$26") (pinfunction "CAN_L_P$26") (pintype "bidirectional"))
      (node (ref "U$2") (pin "P$5") (pinfunction "CAN_L_P$5") (pintype "bidirectional"))
      (node (ref "U101") (pin "6") (pinfunction "CANL_6") (pintype "bidirectional"))
    )
    (net (code "35") (name "Net-(U300-OUTU)") (class "Default")
      (node (ref "JP301") (pin "1") (pinfunction "1_1") (pintype "passive"))
      (node (ref "U300") (pin "3") (pinfunction "OUTU_3") (pintype "output"))
    )
    (net (code "36") (name "Net-(U300-OUTV)") (class "Default")
      (node (ref "JP301") (pin "2") (pinfunction "2_2") (pintype "passive"))
      (node (ref "U300") (pin "8") (pinfunction "OUTV_8") (pintype "output"))
    )
    (net (code "37") (name "Net-(U300-OUTW)") (class "Default")
      (node (ref "JP301") (pin "3") (pinfunction "3_3") (pintype "passive"))
      (node (ref "U300") (pin "10") (pinfunction "OUTW_10") (pintype "output"))
    )
    (net (code "38") (name "Net-(U300-SENSEU)") (class "Default")
      (node (ref "R304") (pin "1") (pinfunction "1_1") (pintype "passive"))
      (node (ref "R305") (pin "2") (pinfunction "2_2") (pintype "passive"))
      (node (ref "R306") (pin "2") (pinfunction "2_2") (pintype "passive"))
      (node (ref "U300") (pin "4") (pinfunction "SENSEU_4") (pintype "output"))
      (node (ref "U300") (pin "9") (pinfunction "SENSEVW_9") (pintype "output"))
    )
    (net (code "39") (name "Net-(U301-IN+)") (class "Default")
      (node (ref "C308") (pin "1") (pinfunction "1_1") (pintype "passive"))
      (node (ref "R303") (pin "1") (pinfunction "1_1") (pintype "passive"))
      (node (ref "R304") (pin "2") (pinfunction "2_2") (pintype "passive"))
      (node (ref "U301") (pin "1") (pinfunction "IN+_1") (pintype "bidirectional"))
    )
    (net (code "40") (name "Net-(U301-IN-)") (class "Default")
      (node (ref "C309") (pin "2") (pinfunction "2_2") (pintype "passive"))
      (node (ref "R307") (pin "1") (pinfunction "1_1") (pintype "passive"))
      (node (ref "R308") (pin "2") (pinfunction "2_2") (pintype "passive"))
      (node (ref "U301") (pin "5") (pinfunction "IN-_5") (pintype "bidirectional"))
    )
    (net (code "41") (name "Net-(U302-MOSI)") (class "Default")
      (node (ref "R309") (pin "2") (pinfunction "2_2") (pintype "passive"))
      (node (ref "U302") (pin "4") (pinfunction "MOSI_4") (pintype "input"))
    )
    (net (code "42") (name "Net-(U400-PH)") (class "Default")
      (node (ref "R403") (pin "1") (pinfunction "1_1") (pintype "passive"))
      (node (ref "U400") (pin "1") (pinfunction "PH_1") (pintype "input"))
    )
    (net (code "43") (name "Net-(U400-PWM)") (class "Default")
      (node (ref "R404") (pin "1") (pinfunction "1_1") (pintype "passive"))
      (node (ref "U400") (pin "2") (pinfunction "PWM_2") (pintype "input"))
    )
    (net (code "44") (name "Net-(U400-REF)") (class "Default")
      (node (ref "C406") (pin "1") (pinfunction "1_1") (pintype "passive"))
      (node (ref "R405") (pin "2") (pinfunction "2_2") (pintype "passive"))
      (node (ref "R406") (pin "1") (pinfunction "1_1") (pintype "passive"))
      (node (ref "U400") (pin "11") (pinfunction "REF_11") (pintype "passive"))
    )
    (net (code "45") (name "Net-(U400-SENSEA)") (class "Default")
      (node (ref "R410") (pin "1") (pinfunction "1_1") (pintype "passive"))
      (node (ref "R411") (pin "1") (pinfunction "1_1") (pintype "passive"))
      (node (ref "R412") (pin "1") (pinfunction "1_1") (pintype "passive"))
      (node (ref "U400") (pin "4") (pinfunction "SENSEA_4") (pintype "output"))
      (node (ref "U400") (pin "9") (pinfunction "SENSEB_9") (pintype "output"))
    )
    (net (code "46") (name "Net-(U400-TOFF)") (class "Default")
      (node (ref "R407") (pin "1") (pinfunction "1_1") (pintype "passive"))
      (node (ref "R408") (pin "1") (pinfunction "1_1") (pintype "passive"))
      (node (ref "U400") (pin "12") (pinfunction "TOFF_12") (pintype "passive"))
    )
    (net (code "47") (name "Net-(U401-IN+)") (class "Default")
      (node (ref "C410") (pin "1") (pinfunction "1_1") (pintype "passive"))
      (node (ref "R409") (pin "1") (pinfunction "1_1") (pintype "passive"))
      (node (ref "R410") (pin "2") (pinfunction "2_2") (pintype "passive"))
      (node (ref "U401") (pin "1") (pinfunction "IN+_1") (pintype "bidirectional"))
    )
    (net (code "48") (name "Net-(U401-IN-)") (class "Default")
      (node (ref "C411") (pin "2") (pinfunction "2_2") (pintype "passive"))
      (node (ref "R413") (pin "1") (pinfunction "1_1") (pintype "passive"))
      (node (ref "R414") (pin "2") (pinfunction "2_2") (pintype "passive"))
      (node (ref "U401") (pin "5") (pinfunction "IN-_5") (pintype "bidirectional"))
    )
    (net (code "49") (name "OUT1") (class "Default")
      (node (ref "U$2") (pin "P$10") (pinfunction "MAG_1_P$10") (pintype "bidirectional"))
      (node (ref "U$2") (pin "P$21") (pinfunction "MAG_1_P$21") (pintype "bidirectional"))
      (node (ref "U400") (pin "10") (pinfunction "OUTB1_10") (pintype "output"))
      (node (ref "U400") (pin "3") (pinfunction "OUTA1_3") (pintype "output"))
    )
    (net (code "50") (name "OUT2") (class "Default")
      (node (ref "U$2") (pin "P$11") (pinfunction "MAG_2_P$11") (pintype "bidirectional"))
      (node (ref "U$2") (pin "P$20") (pinfunction "MAG_2_P$20") (pintype "bidirectional"))
      (node (ref "U400") (pin "5") (pinfunction "OUTA2_5") (pintype "output"))
      (node (ref "U400") (pin "8") (pinfunction "OUTB2_8") (pintype "output"))
    )
    (net (code "51") (name "SPI1_CS") (class "Default")
      (node (ref "U100") (pin "14") (pinfunction "PA4_14") (pintype "bidirectional"))
      (node (ref "U302") (pin "1") (pinfunction "CSN_1") (pintype "input"))
    )
    (net (code "52") (name "SPI1_MISO") (class "Default")
      (node (ref "U100") (pin "16") (pinfunction "PA6_16") (pintype "bidirectional"))
      (node (ref "U302") (pin "3") (pinfunction "MISO_3") (pintype "output"))
    )
    (net (code "53") (name "SPI1_SCK") (class "Default")
      (node (ref "U100") (pin "15") (pinfunction "PA5_15") (pintype "bidirectional"))
      (node (ref "U302") (pin "2") (pinfunction "SCLK_2") (pintype "input"))
    )
    (net (code "54") (name "SWCLK") (class "Default")
      (node (ref "C501") (pin "SWCLK") (pinfunction "9_SWCLK") (pintype "bidirectional"))
      (node (ref "U100") (pin "37") (pinfunction "PA14_37") (pintype "bidirectional"))
    )
    (net (code "55") (name "SWDIO") (class "Default")
      (node (ref "C501") (pin "SWDIO") (pinfunction "8_SWDIO") (pintype "bidirectional"))
      (node (ref "U100") (pin "34") (pinfunction "PA13_34") (pintype "bidirectional"))
    )
    (net (code "56") (name "UART_RX") (class "Default")
      (node (ref "C501") (pin "UART_RX") (pinfunction "5_UART_RX") (pintype "bidirectional"))
      (node (ref "U100") (pin "13") (pinfunction "PA3_13") (pintype "bidirectional"))
    )
    (net (code "57") (name "UART_TX") (class "Default")
      (node (ref "C501") (pin "UART_TX") (pinfunction "6_UART_TX") (pintype "bidirectional"))
      (node (ref "U100") (pin "12") (pinfunction "PA2_12") (pintype "bidirectional"))
    )
    (net (code "58") (name "VBUSP") (class "Default")
      (node (ref "C301") (pin "1") (pinfunction "1_1") (pintype "passive"))
      (node (ref "C302") (pin "1") (pinfunction "1_1") (pintype "passive"))
      (node (ref "C303") (pin "1") (pinfunction "1_1") (pintype "passive"))
      (node (ref "C401") (pin "1") (pinfunction "1_1") (pintype "passive"))
      (node (ref "C402") (pin "1") (pinfunction "1_1") (pintype "passive"))
      (node (ref "C403") (pin "1") (pinfunction "1_1") (pintype "passive"))
      (node (ref "C501") (pin "VBUS") (pinfunction "1_VBUS") (pintype "bidirectional"))
      (node (ref "U$2") (pin "P$12") (pinfunction "VCC_P$12") (pintype "bidirectional"))
      (node (ref "U$2") (pin "P$13") (pinfunction "VCC_P$13") (pintype "bidirectional"))
      (node (ref "U$2") (pin "P$18") (pinfunction "VCC_P$18") (pintype "bidirectional"))
      (node (ref "U$2") (pin "P$19") (pinfunction "VCC_P$19") (pintype "bidirectional"))
      (node (ref "U$2") (pin "P$27") (pinfunction "VCC_P$27") (pintype "bidirectional"))
      (node (ref "U$2") (pin "P$28") (pinfunction "VCC_P$28") (pintype "bidirectional"))
      (node (ref "U$2") (pin "P$3") (pinfunction "VCC_P$3") (pintype "bidirectional"))
      (node (ref "U$2") (pin "P$4") (pinfunction "VCC_P$4") (pintype "bidirectional"))
      (node (ref "U300") (pin "6") (pinfunction "VS_6") (pintype "power_in"))
      (node (ref "U400") (pin "6") (pinfunction "VS_6") (pintype "power_in"))
    )
    (net (code "59") (name "unconnected-(U100-PC13-Pad2)") (class "Default")
      (node (ref "U100") (pin "2") (pinfunction "PC13_2") (pintype "bidirectional"))
    )
    (net (code "60") (name "unconnected-(U100-PC14-OSC32_IN-Pad3)") (class "Default")
      (node (ref "U100") (pin "3") (pinfunction "PC14-OSC32_IN_3") (pintype "bidirectional"))
    )
    (net (code "61") (name "unconnected-(U100-PC15-OSC32_OUT-Pad4)") (class "Default")
      (node (ref "U100") (pin "4") (pinfunction "PC15-OSC32_OUT_4") (pintype "bidirectional"))
    )
    (net (code "62") (name "unconnected-(U101-SHDN-Pad5)") (class "Default")
      (node (ref "U101") (pin "5") (pinfunction "SHDN_5") (pintype "input"))
    )
    (net (code "63") (name "unconnected-(U302-A-Pad7)") (class "Default")
      (node (ref "U302") (pin "7") (pinfunction "A_7") (pintype "output"))
    )
    (net (code "64") (name "unconnected-(U302-B-Pad6)") (class "Default")
      (node (ref "U302") (pin "6") (pinfunction "B_6") (pintype "output"))
    )
    (net (code "65") (name "unconnected-(U302-I{slash}PWM-Pad14)") (class "Default")
      (node (ref "U302") (pin "14") (pinfunction "I/PWM_14") (pintype "output"))
    )
    (net (code "66") (name "unconnected-(U302-U-Pad10)") (class "Default")
      (node (ref "U302") (pin "10") (pinfunction "U_10") (pintype "output"))
    )
    (net (code "67") (name "unconnected-(U302-V-Pad9)") (class "Default")
      (node (ref "U302") (pin "9") (pinfunction "V_9") (pintype "output"))
    )
    (net (code "68") (name "unconnected-(U302-W{slash}PWM-Pad8)") (class "Default")
      (node (ref "U302") (pin "8") (pinfunction "W/PWM_8") (pintype "output"))
    )
  )
)
